# Microcontrolador.net
KiCad netlist of a schematic drawn in Altium Designer
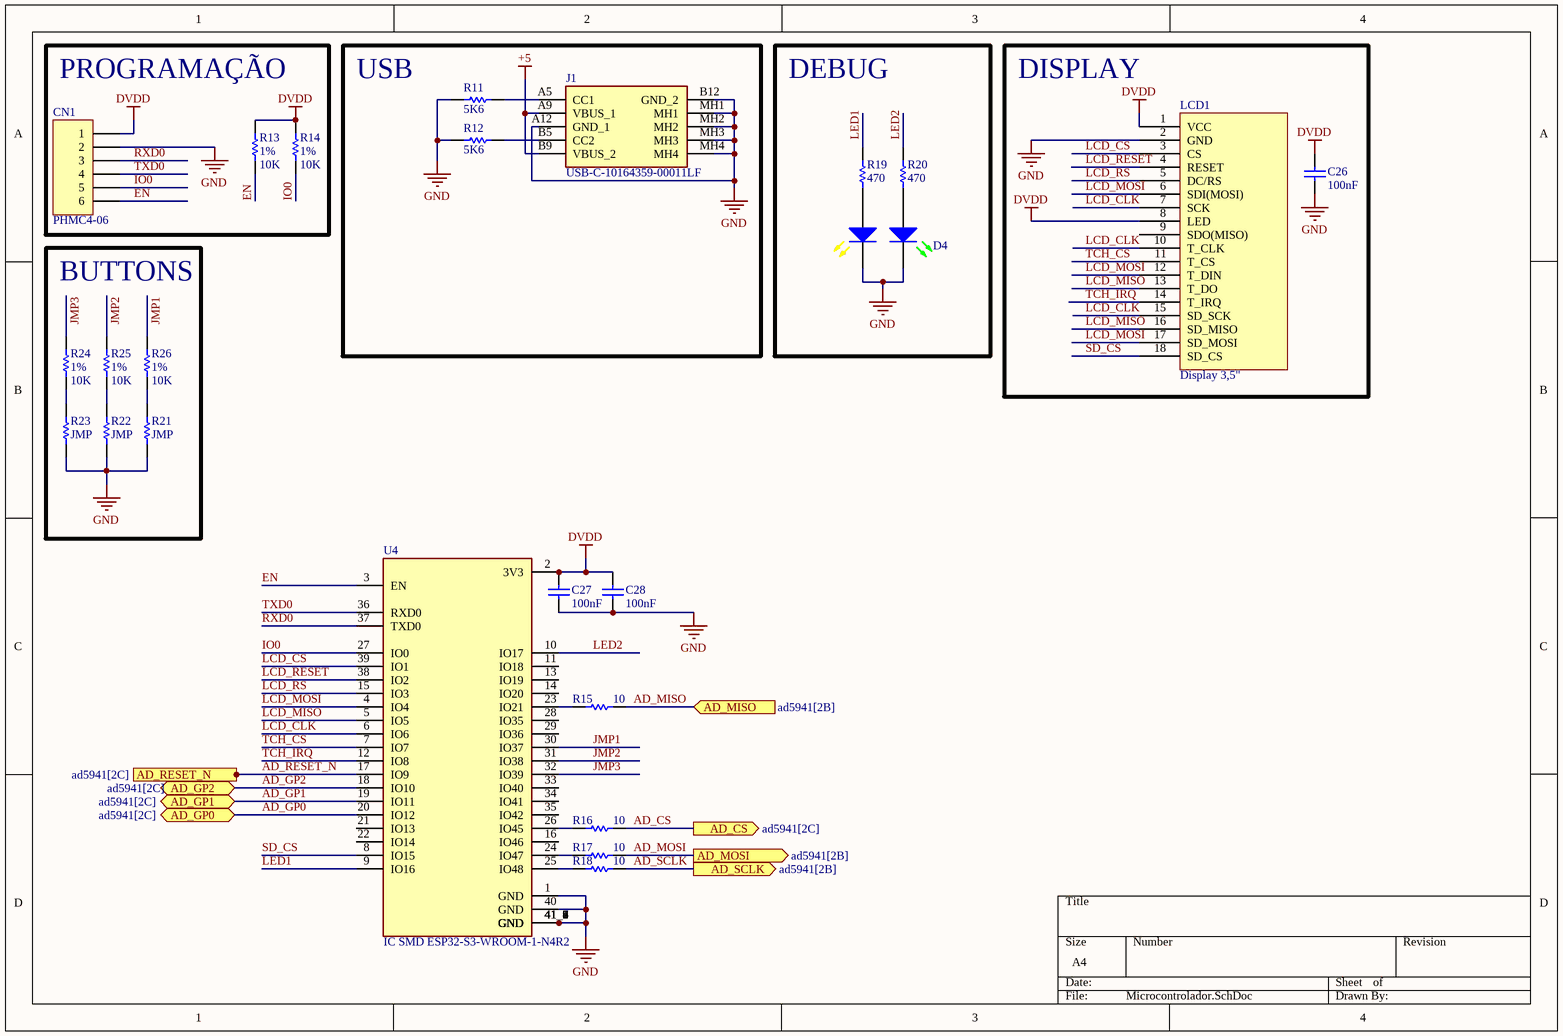
[diagram p0: Microcontrolador.SchDoc]

(export (version "E")
  (design (tool "Eeschema 10.0.6"))
  (components
    (comp (ref "C26")
      (value "100nF")
      (footprint "CAP0805OK")
      (fields
        (field (name "TOLERANCE") "10%")
        (field (name "VOLTAGE") "25V")
        (field (name "Comment") "CAP SMD CER 100NF 25V 0805")
      )
      (libsource (lib "BIB SCH GERAL") (part "CAP SMD CER 100NF 25V 0805"))
    )
    (comp (ref "C27")
      (value "100nF")
      (footprint "CAP0805OK")
      (fields
        (field (name "TOLERANCE") "10%")
        (field (name "VOLTAGE") "25V")
        (field (name "Comment") "CAP SMD CER 100NF 25V 0805")
      )
      (libsource (lib "BIB SCH GERAL") (part "CAP SMD CER 100NF 25V 0805"))
    )
    (comp (ref "C28")
      (value "100nF")
      (footprint "CAP0805OK")
      (fields
        (field (name "TOLERANCE") "10%")
        (field (name "VOLTAGE") "25V")
        (field (name "Comment") "CAP SMD CER 100NF 25V 0805")
      )
      (libsource (lib "BIB SCH GERAL") (part "CAP SMD CER 100NF 25V 0805"))
    )
    (comp (ref "CN1")
      (value "CN MAC 6 VIAS 180º 2.54MM")
      (footprint "PHMC4-06")
      (description "gravação micro")
      (fields (field (name "MANUFACTURER") "METALTEX") (field (name "MANUFACTURER PART NUMBER") "PHMC4-06"))
      (libsource (lib "BIB SCH GERAL") (part "CN MAC 6 VIAS 180º 2.54MM"))
    )
    (comp (ref "D4")
      (value "LED SMD DUAL")
      (footprint "LTST-C197")
      (libsource (lib "BIB SCH GERAL") (part "LED SMD DUAL"))
    )
    (comp (ref "J1")
      (value "USB-C-10164359-00011LF")
      (footprint "LIB_GERAL_V2:USB-C-1016435900011LF")
      (description "Connector")
      (fields
        (field (name "MANUFACTURER_PART_NUMBER") "10164359-00011LF")
        (field (name "MOUSER PART NUMBER") "649-10164359-00011LF")
      )
      (libsource (lib "BIB SCH GERAL") (part "USB-C-10164359-00011LF"))
    )
    (comp (ref "LCD1")
      (value "Display 3,5\"")
      (footprint "Display_3.5\"_SPI_480X320")
      (description "Display TFT SPI 480X320")
      (libsource (lib "BIB SCH GERAL") (part "Display 3,5{dblquote} SPI"))
    )
    (comp (ref "R11")
      (value "5K6")
      (footprint "res0805ok")
      (fields (field (name "TOLERANCE") "1%") (field (name "Comment") "RES SMD 5K6 1% 0805"))
      (libsource (lib "BIB SCH GERAL") (part "RES SMD 10K 1% 0805"))
    )
    (comp (ref "R12")
      (value "5K6")
      (footprint "res0805ok")
      (fields (field (name "TOLERANCE") "1%") (field (name "Comment") "RES SMD 5K6 1% 0805"))
      (libsource (lib "BIB SCH GERAL") (part "RES SMD 10K 1% 0805"))
    )
    (comp (ref "R13")
      (value "10K")
      (footprint "res0805ok")
      (fields (field (name "TOLERANCE") "1%") (field (name "Comment") "RES SMD 10K 1% 0805"))
      (libsource (lib "BIB SCH GERAL") (part "RES SMD 10K 1% 0805"))
    )
    (comp (ref "R14")
      (value "10K")
      (footprint "res0805ok")
      (fields (field (name "TOLERANCE") "1%") (field (name "Comment") "RES SMD 10K 1% 0805"))
      (libsource (lib "BIB SCH GERAL") (part "RES SMD 10K 1% 0805"))
    )
    (comp (ref "R15")
      (value "10")
      (footprint "res0805ok")
      (fields (field (name "TOLERANCE") "1%") (field (name "Comment") "RES SMD 10 1% 0805"))
      (libsource (lib "BIB SCH GERAL") (part "RES SMD 10K 1% 0805"))
    )
    (comp (ref "R16")
      (value "10")
      (footprint "res0805ok")
      (fields (field (name "TOLERANCE") "1%") (field (name "Comment") "RES SMD 10 1% 0805"))
      (libsource (lib "BIB SCH GERAL") (part "RES SMD 10K 1% 0805"))
    )
    (comp (ref "R17")
      (value "10")
      (footprint "res0805ok")
      (fields (field (name "TOLERANCE") "1%") (field (name "Comment") "RES SMD 10 1% 0805"))
      (libsource (lib "BIB SCH GERAL") (part "RES SMD 10K 1% 0805"))
    )
    (comp (ref "R18")
      (value "10")
      (footprint "res0805ok")
      (fields (field (name "TOLERANCE") "1%") (field (name "Comment") "RES SMD 10 1% 0805"))
      (libsource (lib "BIB SCH GERAL") (part "RES SMD 10K 1% 0805"))
    )
    (comp (ref "R19")
      (value "470")
      (footprint "res0805ok")
      (fields (field (name "TOLERANCE") "1%") (field (name "Comment") "RES SMD 1K 1% 0805"))
      (libsource (lib "BIB SCH GERAL") (part "RES SMD 1K 1% 0805"))
    )
    (comp (ref "R20")
      (value "470")
      (footprint "res0805ok")
      (fields (field (name "TOLERANCE") "1%") (field (name "Comment") "RES SMD 1K 1% 0805"))
      (libsource (lib "BIB SCH GERAL") (part "RES SMD 1K 1% 0805"))
    )
    (comp (ref "R21")
      (value "JMP")
      (footprint "JMP0805")
      (fields (field (name "TOLERANCE") "1%") (field (name "Comment") "RES SMD 10K 1% 0805"))
      (libsource (lib "BIB SCH GERAL") (part "RES SMD 10K 1% 0805"))
    )
    (comp (ref "R22")
      (value "JMP")
      (footprint "JMP0805")
      (fields (field (name "TOLERANCE") "1%") (field (name "Comment") "RES SMD 10K 1% 0805"))
      (libsource (lib "BIB SCH GERAL") (part "RES SMD 10K 1% 0805"))
    )
    (comp (ref "R23")
      (value "JMP")
      (footprint "JMP0805")
      (fields (field (name "TOLERANCE") "1%") (field (name "Comment") "RES SMD 10K 1% 0805"))
      (libsource (lib "BIB SCH GERAL") (part "RES SMD 10K 1% 0805"))
    )
    (comp (ref "R24")
      (value "10K")
      (footprint "res0805ok")
      (fields (field (name "TOLERANCE") "1%") (field (name "Comment") "RES SMD 10K 1% 0805"))
      (libsource (lib "BIB SCH GERAL") (part "RES SMD 10K 1% 0805"))
    )
    (comp (ref "R25")
      (value "10K")
      (footprint "res0805ok")
      (fields (field (name "TOLERANCE") "1%") (field (name "Comment") "RES SMD 10K 1% 0805"))
      (libsource (lib "BIB SCH GERAL") (part "RES SMD 10K 1% 0805"))
    )
    (comp (ref "R26")
      (value "10K")
      (footprint "res0805ok")
      (fields (field (name "TOLERANCE") "1%") (field (name "Comment") "RES SMD 10K 1% 0805"))
      (libsource (lib "BIB SCH GERAL") (part "RES SMD 10K 1% 0805"))
    )
    (comp (ref "U4")
      (value "IC SMD ESP32-S3-WROOM-1-N4R2")
      (footprint "XCVR_ESP32-S3-WROOM-1-N4R2")
      (description "Bluetooth, WiFi 802.11b/g/n, Bluetooth v5.0 Transceiver Module 2.4GHz PCB Trace Surface Mount")
      (fields (field (name "MF") "Espressif Systems") (field (name "MP") "ESP32-S3-WROOM-1-N4R2"))
      (libsource (lib "BIB SCH GERAL") (part "IC SMD ESP32-S3-WROOM-1-N4R2"))
    )
  )
  (nets
    (net (code "1") (name "+5") (class "Default")
      (node (ref "J1") (pin "A9") (pinfunction "VBUS_1_A9") (pintype "passive"))
      (node (ref "J1") (pin "B9") (pinfunction "VBUS_2_B9") (pintype "passive"))
    )
    (net (code "2") (name "/AD_CS") (class "Default")
      (node (ref "R16") (pin "1") (pinfunction "1_1") (pintype "passive"))
    )
    (net (code "3") (name "/AD_GP0") (class "Default")
      (node (ref "U4") (pin "20") (pinfunction "IO12_20") (pintype "passive"))
    )
    (net (code "4") (name "/AD_GP1") (class "Default")
      (node (ref "U4") (pin "19") (pinfunction "IO11_19") (pintype "passive"))
    )
    (net (code "5") (name "/AD_GP2") (class "Default")
      (node (ref "U4") (pin "18") (pinfunction "IO10_18") (pintype "passive"))
    )
    (net (code "6") (name "/AD_MISO") (class "Default")
      (node (ref "R15") (pin "1") (pinfunction "1_1") (pintype "passive"))
    )
    (net (code "7") (name "/AD_MOSI") (class "Default")
      (node (ref "R17") (pin "1") (pinfunction "1_1") (pintype "passive"))
    )
    (net (code "8") (name "/AD_RESET_N") (class "Default")
      (node (ref "U4") (pin "17") (pinfunction "IO9_17") (pintype "passive"))
    )
    (net (code "9") (name "/AD_SCLK") (class "Default")
      (node (ref "R18") (pin "1") (pinfunction "1_1") (pintype "passive"))
    )
    (net (code "10") (name "/EN") (class "Default")
      (node (ref "CN1") (pin "6") (pinfunction "6_6") (pintype "passive"))
      (node (ref "R13") (pin "1") (pinfunction "1_1") (pintype "passive"))
      (node (ref "U4") (pin "3") (pinfunction "EN_3") (pintype "passive"))
    )
    (net (code "11") (name "/IO0") (class "Default")
      (node (ref "CN1") (pin "5") (pinfunction "5_5") (pintype "passive"))
      (node (ref "R14") (pin "1") (pinfunction "1_1") (pintype "passive"))
      (node (ref "U4") (pin "27") (pinfunction "IO0_27") (pintype "passive"))
    )
    (net (code "12") (name "/JMP1") (class "Default")
      (node (ref "R26") (pin "2") (pinfunction "2_2") (pintype "passive"))
      (node (ref "U4") (pin "30") (pinfunction "IO37_30") (pintype "passive"))
    )
    (net (code "13") (name "/JMP2") (class "Default")
      (node (ref "R25") (pin "2") (pinfunction "2_2") (pintype "passive"))
      (node (ref "U4") (pin "31") (pinfunction "IO38_31") (pintype "passive"))
    )
    (net (code "14") (name "/JMP3") (class "Default")
      (node (ref "R24") (pin "2") (pinfunction "2_2") (pintype "passive"))
      (node (ref "U4") (pin "32") (pinfunction "IO39_32") (pintype "passive"))
    )
    (net (code "15") (name "/LCD_CLK") (class "Default")
      (node (ref "LCD1") (pin "10") (pinfunction "T_CLK_10") (pintype "passive"))
      (node (ref "LCD1") (pin "15") (pinfunction "SD_SCK_15") (pintype "passive"))
      (node (ref "LCD1") (pin "7") (pinfunction "SCK_7") (pintype "passive"))
      (node (ref "U4") (pin "6") (pinfunction "IO6_6") (pintype "passive"))
    )
    (net (code "16") (name "/LCD_CS") (class "Default")
      (node (ref "LCD1") (pin "3") (pinfunction "CS_3") (pintype "passive"))
      (node (ref "U4") (pin "39") (pinfunction "IO1_39") (pintype "passive"))
    )
    (net (code "17") (name "/LCD_MISO") (class "Default")
      (node (ref "LCD1") (pin "13") (pinfunction "T_DO_13") (pintype "passive"))
      (node (ref "LCD1") (pin "16") (pinfunction "SD_MISO_16") (pintype "passive"))
      (node (ref "U4") (pin "5") (pinfunction "IO5_5") (pintype "passive"))
    )
    (net (code "18") (name "/LCD_MOSI") (class "Default")
      (node (ref "LCD1") (pin "12") (pinfunction "T_DIN_12") (pintype "passive"))
      (node (ref "LCD1") (pin "17") (pinfunction "SD_MOSI_17") (pintype "passive"))
      (node (ref "LCD1") (pin "6") (pinfunction "SDI(MOSI)_6") (pintype "passive"))
      (node (ref "U4") (pin "4") (pinfunction "IO4_4") (pintype "passive"))
    )
    (net (code "19") (name "/LCD_RESET") (class "Default")
      (node (ref "LCD1") (pin "4") (pinfunction "RESET_4") (pintype "passive"))
      (node (ref "U4") (pin "38") (pinfunction "IO2_38") (pintype "passive"))
    )
    (net (code "20") (name "/LCD_RS") (class "Default")
      (node (ref "LCD1") (pin "5") (pinfunction "DC/RS_5") (pintype "passive"))
      (node (ref "U4") (pin "15") (pinfunction "IO3_15") (pintype "passive"))
    )
    (net (code "21") (name "/LED1") (class "Default")
      (node (ref "R19") (pin "2") (pinfunction "2_2") (pintype "passive"))
      (node (ref "U4") (pin "9") (pinfunction "IO16_9") (pintype "passive"))
    )
    (net (code "22") (name "/LED2") (class "Default")
      (node (ref "R20") (pin "2") (pinfunction "2_2") (pintype "passive"))
      (node (ref "U4") (pin "10") (pinfunction "IO17_10") (pintype "passive"))
    )
    (net (code "23") (name "/RXD0") (class "Default")
      (node (ref "CN1") (pin "3") (pinfunction "3_3") (pintype "passive"))
      (node (ref "U4") (pin "37") (pinfunction "TXD0_37") (pintype "passive"))
    )
    (net (code "24") (name "/SD_CS") (class "Default")
      (node (ref "LCD1") (pin "18") (pinfunction "SD_CS_18") (pintype "passive"))
      (node (ref "U4") (pin "8") (pinfunction "IO15_8") (pintype "passive"))
    )
    (net (code "25") (name "/TCH_CS") (class "Default")
      (node (ref "LCD1") (pin "11") (pinfunction "T_CS_11") (pintype "passive"))
      (node (ref "U4") (pin "7") (pinfunction "IO7_7") (pintype "passive"))
    )
    (net (code "26") (name "/TCH_IRQ") (class "Default")
      (node (ref "LCD1") (pin "14") (pinfunction "T_IRQ_14") (pintype "passive"))
      (node (ref "U4") (pin "12") (pinfunction "IO8_12") (pintype "passive"))
    )
    (net (code "27") (name "/TXD0") (class "Default")
      (node (ref "CN1") (pin "4") (pinfunction "4_4") (pintype "passive"))
      (node (ref "U4") (pin "36") (pinfunction "RXD0_36") (pintype "passive"))
    )
    (net (code "28") (name "DVDD") (class "Default")
      (node (ref "C26") (pin "2") (pinfunction "2_2") (pintype "passive"))
      (node (ref "C27") (pin "1") (pinfunction "1_1") (pintype "passive"))
      (node (ref "C28") (pin "1") (pinfunction "1_1") (pintype "passive"))
      (node (ref "CN1") (pin "1") (pinfunction "1_1") (pintype "passive"))
      (node (ref "LCD1") (pin "1") (pinfunction "VCC_1") (pintype "power_in"))
      (node (ref "LCD1") (pin "8") (pinfunction "LED_8") (pintype "passive"))
      (node (ref "R13") (pin "2") (pinfunction "2_2") (pintype "passive"))
      (node (ref "R14") (pin "2") (pinfunction "2_2") (pintype "passive"))
      (node (ref "U4") (pin "2") (pinfunction "3V3_2") (pintype "power_in"))
    )
    (net (code "29") (name "GND") (class "Default")
      (node (ref "C26") (pin "1") (pinfunction "1_1") (pintype "passive"))
      (node (ref "C27") (pin "2") (pinfunction "2_2") (pintype "passive"))
      (node (ref "C28") (pin "2") (pinfunction "2_2") (pintype "passive"))
      (node (ref "CN1") (pin "2") (pinfunction "2_2") (pintype "passive"))
      (node (ref "D4") (pin "3") (pinfunction "K_3") (pintype "passive"))
      (node (ref "D4") (pin "4") (pinfunction "K_4") (pintype "passive"))
      (node (ref "J1") (pin "A12") (pinfunction "GND_1_A12") (pintype "passive"))
      (node (ref "J1") (pin "B12") (pinfunction "GND_2_B12") (pintype "passive"))
      (node (ref "J1") (pin "MH1") (pinfunction "MH1_MH1") (pintype "passive"))
      (node (ref "J1") (pin "MH2") (pinfunction "MH2_MH2") (pintype "passive"))
      (node (ref "J1") (pin "MH3") (pinfunction "MH3_MH3") (pintype "passive"))
      (node (ref "J1") (pin "MH4") (pinfunction "MH4_MH4") (pintype "passive"))
      (node (ref "LCD1") (pin "2") (pinfunction "GND_2") (pintype "power_in"))
      (node (ref "R11") (pin "2") (pinfunction "2_2") (pintype "passive"))
      (node (ref "R12") (pin "2") (pinfunction "2_2") (pintype "passive"))
      (node (ref "R21") (pin "2") (pinfunction "2_2") (pintype "passive"))
      (node (ref "R22") (pin "2") (pinfunction "2_2") (pintype "passive"))
      (node (ref "R23") (pin "2") (pinfunction "2_2") (pintype "passive"))
      (node (ref "U4") (pin "1") (pinfunction "GND_1") (pintype "power_in"))
      (node (ref "U4") (pin "40") (pinfunction "GND_40") (pintype "power_in"))
      (node (ref "U4") (pin "41_1") (pinfunction "GND_41_1") (pintype "power_in"))
      (node (ref "U4") (pin "41_2") (pinfunction "GND_41_2") (pintype "power_in"))
      (node (ref "U4") (pin "41_3") (pinfunction "GND_41_3") (pintype "power_in"))
      (node (ref "U4") (pin "41_4") (pinfunction "GND_41_4") (pintype "power_in"))
      (node (ref "U4") (pin "41_5") (pinfunction "GND_41_5") (pintype "power_in"))
      (node (ref "U4") (pin "41_6") (pinfunction "GND_41_6") (pintype "power_in"))
      (node (ref "U4") (pin "41_7") (pinfunction "GND_41_7") (pintype "power_in"))
      (node (ref "U4") (pin "41_8") (pinfunction "GND_41_8") (pintype "power_in"))
      (node (ref "U4") (pin "41_9") (pinfunction "GND_41_9") (pintype "power_in"))
    )
    (net (code "30") (name "Net-(D4-A-Pad1)") (class "Default")
      (node (ref "D4") (pin "1") (pinfunction "A_1") (pintype "passive"))
      (node (ref "R20") (pin "1") (pinfunction "1_1") (pintype "passive"))
    )
    (net (code "31") (name "Net-(D4-A-Pad2)") (class "Default")
      (node (ref "D4") (pin "2") (pinfunction "A_2") (pintype "passive"))
      (node (ref "R19") (pin "1") (pinfunction "1_1") (pintype "passive"))
    )
    (net (code "32") (name "Net-(J1-CC1)") (class "Default")
      (node (ref "J1") (pin "A5") (pinfunction "CC1_A5") (pintype "passive"))
      (node (ref "R11") (pin "1") (pinfunction "1_1") (pintype "passive"))
    )
    (net (code "33") (name "Net-(J1-CC2)") (class "Default")
      (node (ref "J1") (pin "B5") (pinfunction "CC2_B5") (pintype "passive"))
      (node (ref "R12") (pin "1") (pinfunction "1_1") (pintype "passive"))
    )
    (net (code "34") (name "Net-(R21-Pad1)") (class "Default")
      (node (ref "R21") (pin "1") (pinfunction "1_1") (pintype "passive"))
      (node (ref "R26") (pin "1") (pinfunction "1_1") (pintype "passive"))
    )
    (net (code "35") (name "Net-(R22-Pad1)") (class "Default")
      (node (ref "R22") (pin "1") (pinfunction "1_1") (pintype "passive"))
      (node (ref "R25") (pin "1") (pinfunction "1_1") (pintype "passive"))
    )
    (net (code "36") (name "Net-(R23-Pad1)") (class "Default")
      (node (ref "R23") (pin "1") (pinfunction "1_1") (pintype "passive"))
      (node (ref "R24") (pin "1") (pinfunction "1_1") (pintype "passive"))
    )
    (net (code "37") (name "Net-(U4-IO21)") (class "Default")
      (node (ref "R15") (pin "2") (pinfunction "2_2") (pintype "passive"))
      (node (ref "U4") (pin "23") (pinfunction "IO21_23") (pintype "passive"))
    )
    (net (code "38") (name "Net-(U4-IO45)") (class "Default")
      (node (ref "R16") (pin "2") (pinfunction "2_2") (pintype "passive"))
      (node (ref "U4") (pin "26") (pinfunction "IO45_26") (pintype "passive"))
    )
    (net (code "39") (name "Net-(U4-IO47)") (class "Default")
      (node (ref "R17") (pin "2") (pinfunction "2_2") (pintype "passive"))
      (node (ref "U4") (pin "24") (pinfunction "IO47_24") (pintype "passive"))
    )
    (net (code "40") (name "Net-(U4-IO48)") (class "Default")
      (node (ref "R18") (pin "2") (pinfunction "2_2") (pintype "passive"))
      (node (ref "U4") (pin "25") (pinfunction "IO48_25") (pintype "passive"))
    )
    (net (code "41") (name "unconnected-(LCD1-SDO(MISO)-Pad9)") (class "Default")
      (node (ref "LCD1") (pin "9") (pinfunction "SDO(MISO)_9") (pintype "passive"))
    )
    (net (code "42") (name "unconnected-(U4-IO13-Pad21)") (class "Default")
      (node (ref "U4") (pin "21") (pinfunction "IO13_21") (pintype "passive"))
    )
    (net (code "43") (name "unconnected-(U4-IO14-Pad22)") (class "Default")
      (node (ref "U4") (pin "22") (pinfunction "IO14_22") (pintype "passive"))
    )
    (net (code "44") (name "unconnected-(U4-IO18-Pad11)") (class "Default")
      (node (ref "U4") (pin "11") (pinfunction "IO18_11") (pintype "passive"))
    )
    (net (code "45") (name "unconnected-(U4-IO19-Pad13)") (class "Default")
      (node (ref "U4") (pin "13") (pinfunction "IO19_13") (pintype "passive"))
    )
    (net (code "46") (name "unconnected-(U4-IO20-Pad14)") (class "Default")
      (node (ref "U4") (pin "14") (pinfunction "IO20_14") (pintype "passive"))
    )
    (net (code "47") (name "unconnected-(U4-IO35-Pad28)") (class "Default")
      (node (ref "U4") (pin "28") (pinfunction "IO35_28") (pintype "passive"))
    )
    (net (code "48") (name "unconnected-(U4-IO36-Pad29)") (class "Default")
      (node (ref "U4") (pin "29") (pinfunction "IO36_29") (pintype "passive"))
    )
    (net (code "49") (name "unconnected-(U4-IO40-Pad33)") (class "Default")
      (node (ref "U4") (pin "33") (pinfunction "IO40_33") (pintype "passive"))
    )
    (net (code "50") (name "unconnected-(U4-IO41-Pad34)") (class "Default")
      (node (ref "U4") (pin "34") (pinfunction "IO41_34") (pintype "passive"))
    )
    (net (code "51") (name "unconnected-(U4-IO42-Pad35)") (class "Default")
      (node (ref "U4") (pin "35") (pinfunction "IO42_35") (pintype "passive"))
    )
    (net (code "52") (name "unconnected-(U4-IO46-Pad16)") (class "Default")
      (node (ref "U4") (pin "16") (pinfunction "IO46_16") (pintype "passive"))
    )
  )
)
